# E-Slushy.net
KiCad netlist of a schematic drawn in EAGLE
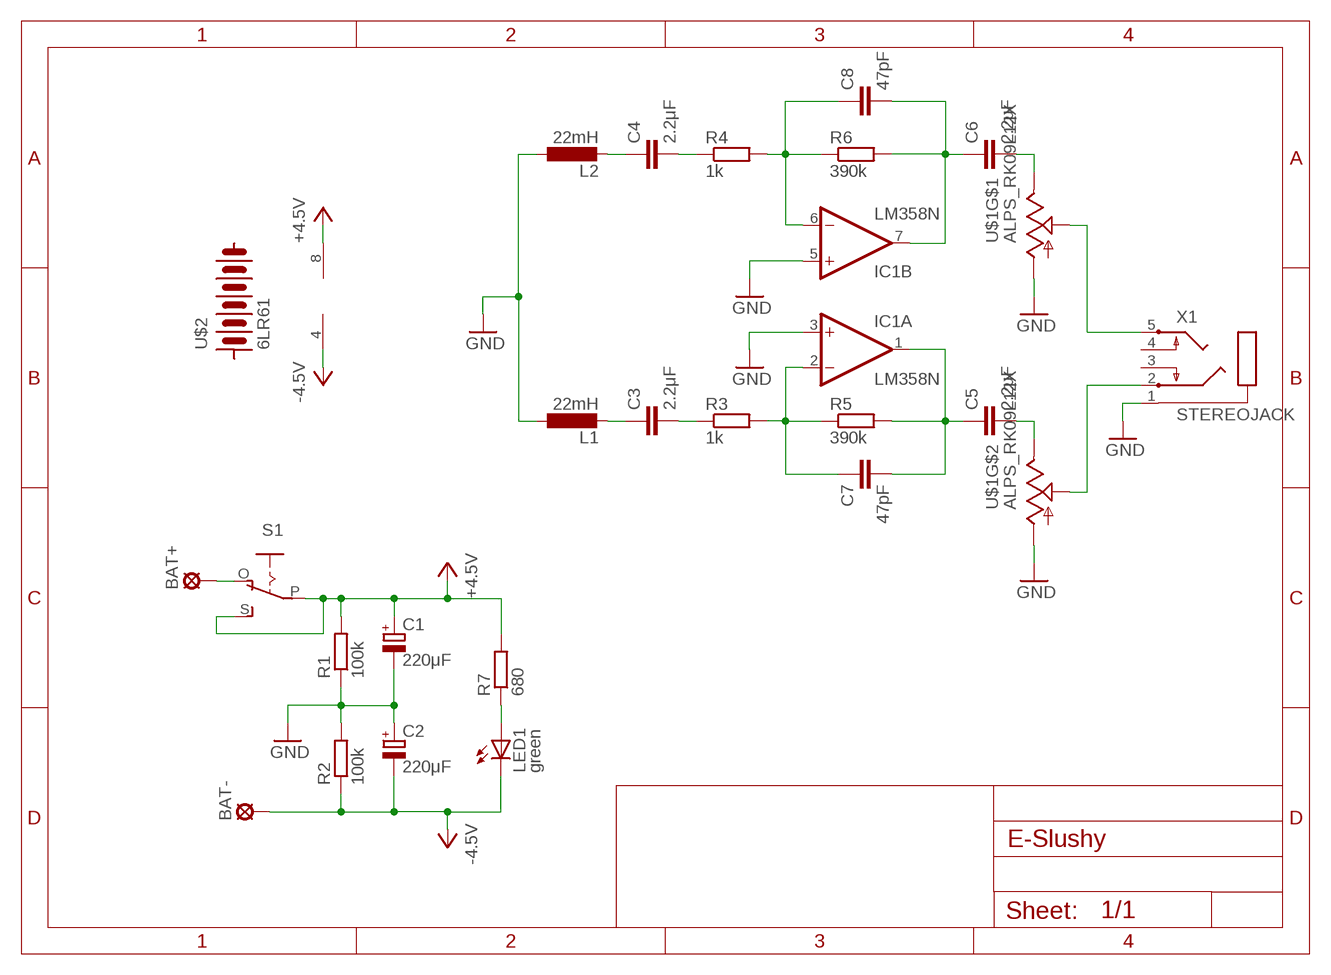
[diagram p0: schematic, sheet 1]

(export (version "E")
  (design (tool "Eeschema 10.0.6"))
  (components
    (comp (ref "BAT+")
      (value "SE14")
      (footprint "eagle-import:SE14")
      (libsource (lib "eagle-import") (part "SE14"))
    )
    (comp (ref "BAT-")
      (value "SE14")
      (footprint "eagle-import:SE14")
      (libsource (lib "eagle-import") (part "SE14"))
    )
    (comp (ref "C1")
      (value "220μF")
      (footprint "eagle-import:PANASONIC_D")
      (libsource (lib "eagle-import") (part "CPOL-EUD"))
    )
    (comp (ref "C2")
      (value "220μF")
      (footprint "eagle-import:PANASONIC_D")
      (libsource (lib "eagle-import") (part "CPOL-EUD"))
    )
    (comp (ref "C3")
      (value "2.2μF")
      (footprint "eagle-import:C1206K")
      (libsource (lib "eagle-import") (part "C-EUC1206K"))
    )
    (comp (ref "C4")
      (value "2.2μF")
      (footprint "eagle-import:C1206K")
      (libsource (lib "eagle-import") (part "C-EUC1206K"))
    )
    (comp (ref "C5")
      (value "2.2μF")
      (footprint "eagle-import:C1206K")
      (libsource (lib "eagle-import") (part "C-EUC1206K"))
    )
    (comp (ref "C6")
      (value "2.2μF")
      (footprint "eagle-import:C1206K")
      (libsource (lib "eagle-import") (part "C-EUC1206K"))
    )
    (comp (ref "C7")
      (value "47pF")
      (footprint "eagle-import:C1206K")
      (libsource (lib "eagle-import") (part "C-EUC1206K"))
    )
    (comp (ref "C8")
      (value "47pF")
      (footprint "eagle-import:C1206K")
      (libsource (lib "eagle-import") (part "C-EUC1206K"))
    )
    (comp (ref "IC1")
      (value "LM358N")
      (footprint "eagle-import:DIL08")
      (libsource (lib "eagle-import") (part "LM358N"))
    )
    (comp (ref "L1")
      (value "22mH")
      (footprint "eagle-import:6000-XXXX-RC")
      (libsource (lib "eagle-import") (part "L-EU6000-XXX-RC"))
    )
    (comp (ref "L2")
      (value "22mH")
      (footprint "eagle-import:6000-XXXX-RC")
      (libsource (lib "eagle-import") (part "L-EU6000-XXX-RC"))
    )
    (comp (ref "LED1")
      (value "green")
      (footprint "eagle-import:LED5MM")
      (libsource (lib "eagle-import") (part "LED5MM"))
    )
    (comp (ref "R1")
      (value "100k")
      (footprint "eagle-import:R1206")
      (libsource (lib "eagle-import") (part "R-EU_R1206"))
    )
    (comp (ref "R2")
      (value "100k")
      (footprint "eagle-import:R1206")
      (libsource (lib "eagle-import") (part "R-EU_R1206"))
    )
    (comp (ref "R3")
      (value "1k")
      (footprint "eagle-import:R1206")
      (libsource (lib "eagle-import") (part "R-EU_R1206"))
    )
    (comp (ref "R4")
      (value "1k")
      (footprint "eagle-import:R1206")
      (libsource (lib "eagle-import") (part "R-EU_R1206"))
    )
    (comp (ref "R5")
      (value "390k")
      (footprint "eagle-import:R1206")
      (libsource (lib "eagle-import") (part "R-EU_R1206"))
    )
    (comp (ref "R6")
      (value "390k")
      (footprint "eagle-import:R1206")
      (libsource (lib "eagle-import") (part "R-EU_R1206"))
    )
    (comp (ref "R7")
      (value "680")
      (footprint "eagle-import:R1206")
      (libsource (lib "eagle-import") (part "R-EU_R1206"))
    )
    (comp (ref "S1")
      (value "EG1218S")
      (footprint "eagle-import:EG1218")
      (libsource (lib "eagle-import") (part "EG1218S"))
    )
    (comp (ref "U$1")
      (value "ALPS_RK09L12X")
      (footprint "eagle-import:RK09L12")
      (libsource (lib "eagle-import") (part "ALPS_RK09L12X"))
    )
    (comp (ref "U$2")
      (value "6LR61")
      (footprint "eagle-import:6LR61")
      (libsource (lib "eagle-import") (part "6LR61"))
    )
    (comp (ref "X1")
      (value "STEREOJACK")
      (footprint "eagle-import:STX3100")
      (libsource (lib "eagle-import") (part "STEREOJACK"))
    )
  )
  (nets
    (net (code "1") (name "+4.5V") (class "Default")
      (node (ref "C1") (pin "+") (pinfunction "+_+") (pintype "passive"))
      (node (ref "IC1") (pin "8") (pinfunction "V+_8") (pintype "power_in"))
      (node (ref "R1") (pin "2") (pinfunction "2_2") (pintype "passive"))
      (node (ref "R7") (pin "2") (pinfunction "2_2") (pintype "passive"))
      (node (ref "S1") (pin "P") (pinfunction "P_P") (pintype "passive"))
      (node (ref "S1") (pin "S") (pinfunction "S_S") (pintype "passive"))
    )
    (net (code "2") (name "-4.5V") (class "Default")
      (node (ref "BAT-") (pin "MP") (pinfunction "MP_MP") (pintype "passive"))
      (node (ref "C2") (pin "-") (pinfunction "-_-") (pintype "passive"))
      (node (ref "IC1") (pin "4") (pinfunction "V-_4") (pintype "power_in"))
      (node (ref "LED1") (pin "K") (pinfunction "C_K") (pintype "passive"))
      (node (ref "R2") (pin "1") (pinfunction "1_1") (pintype "passive"))
    )
    (net (code "3") (name "GND") (class "Default")
      (node (ref "C1") (pin "-") (pinfunction "-_-") (pintype "passive"))
      (node (ref "C2") (pin "+") (pinfunction "+_+") (pintype "passive"))
      (node (ref "IC1") (pin "3") (pinfunction "+IN_3") (pintype "input"))
      (node (ref "IC1") (pin "5") (pinfunction "+IN_5") (pintype "input"))
      (node (ref "L1") (pin "1") (pinfunction "1_1") (pintype "passive"))
      (node (ref "L2") (pin "1") (pinfunction "1_1") (pintype "passive"))
      (node (ref "R1") (pin "1") (pinfunction "1_1") (pintype "passive"))
      (node (ref "R2") (pin "2") (pinfunction "2_2") (pintype "passive"))
      (node (ref "U$1") (pin "A1") (pinfunction "1_A1") (pintype "passive"))
      (node (ref "U$1") (pin "B1") (pinfunction "1_B1") (pintype "passive"))
      (node (ref "X1") (pin "1") (pinfunction "1_1") (pintype "passive"))
    )
    (net (code "4") (name "Net-(BAT+-PadMP)") (class "Default")
      (node (ref "BAT+") (pin "MP") (pinfunction "MP_MP") (pintype "passive"))
      (node (ref "S1") (pin "O") (pinfunction "O_O") (pintype "passive"))
    )
    (net (code "5") (name "Net-(C3-Pad1)") (class "Default")
      (node (ref "C3") (pin "1") (pinfunction "1_1") (pintype "passive"))
      (node (ref "L1") (pin "2") (pinfunction "2_2") (pintype "passive"))
    )
    (net (code "6") (name "Net-(C3-Pad2)") (class "Default")
      (node (ref "C3") (pin "2") (pinfunction "2_2") (pintype "passive"))
      (node (ref "R3") (pin "1") (pinfunction "1_1") (pintype "passive"))
    )
    (net (code "7") (name "Net-(C4-Pad1)") (class "Default")
      (node (ref "C4") (pin "1") (pinfunction "1_1") (pintype "passive"))
      (node (ref "L2") (pin "2") (pinfunction "2_2") (pintype "passive"))
    )
    (net (code "8") (name "Net-(C4-Pad2)") (class "Default")
      (node (ref "C4") (pin "2") (pinfunction "2_2") (pintype "passive"))
      (node (ref "R4") (pin "1") (pinfunction "1_1") (pintype "passive"))
    )
    (net (code "9") (name "Net-(IC1A--IN)") (class "Default")
      (node (ref "C7") (pin "1") (pinfunction "1_1") (pintype "passive"))
      (node (ref "IC1") (pin "2") (pinfunction "-IN_2") (pintype "input"))
      (node (ref "R3") (pin "2") (pinfunction "2_2") (pintype "passive"))
      (node (ref "R5") (pin "1") (pinfunction "1_1") (pintype "passive"))
    )
    (net (code "10") (name "Net-(IC1A-OUT)") (class "Default")
      (node (ref "C5") (pin "1") (pinfunction "1_1") (pintype "passive"))
      (node (ref "C7") (pin "2") (pinfunction "2_2") (pintype "passive"))
      (node (ref "IC1") (pin "1") (pinfunction "OUT_1") (pintype "output"))
      (node (ref "R5") (pin "2") (pinfunction "2_2") (pintype "passive"))
    )
    (net (code "11") (name "Net-(IC1B--IN)") (class "Default")
      (node (ref "C8") (pin "1") (pinfunction "1_1") (pintype "passive"))
      (node (ref "IC1") (pin "6") (pinfunction "-IN_6") (pintype "input"))
      (node (ref "R4") (pin "2") (pinfunction "2_2") (pintype "passive"))
      (node (ref "R6") (pin "1") (pinfunction "1_1") (pintype "passive"))
    )
    (net (code "12") (name "Net-(IC1B-OUT)") (class "Default")
      (node (ref "C6") (pin "1") (pinfunction "1_1") (pintype "passive"))
      (node (ref "C8") (pin "2") (pinfunction "2_2") (pintype "passive"))
      (node (ref "IC1") (pin "7") (pinfunction "OUT_7") (pintype "output"))
      (node (ref "R6") (pin "2") (pinfunction "2_2") (pintype "passive"))
    )
    (net (code "13") (name "Net-(LED1-PadA)") (class "Default")
      (node (ref "LED1") (pin "A") (pinfunction "A_A") (pintype "passive"))
      (node (ref "R7") (pin "1") (pinfunction "1_1") (pintype "passive"))
    )
    (net (code "14") (name "Net-(U$1A-2)") (class "Default")
      (node (ref "U$1") (pin "A2") (pinfunction "2_A2") (pintype "passive"))
      (node (ref "X1") (pin "5") (pinfunction "5_5") (pintype "passive"))
    )
    (net (code "15") (name "Net-(U$1A-3)") (class "Default")
      (node (ref "C6") (pin "2") (pinfunction "2_2") (pintype "passive"))
      (node (ref "U$1") (pin "A3") (pinfunction "3_A3") (pintype "passive"))
    )
    (net (code "16") (name "Net-(U$1B-2)") (class "Default")
      (node (ref "U$1") (pin "B2") (pinfunction "2_B2") (pintype "passive"))
      (node (ref "X1") (pin "2") (pinfunction "2_2") (pintype "passive"))
    )
    (net (code "17") (name "Net-(U$1B-3)") (class "Default")
      (node (ref "C5") (pin "2") (pinfunction "2_2") (pintype "passive"))
      (node (ref "U$1") (pin "B3") (pinfunction "3_B3") (pintype "passive"))
    )
    (net (code "18") (name "unconnected-(X1-Pad3)") (class "Default")
      (node (ref "X1") (pin "3") (pinfunction "3_3") (pintype "passive"))
    )
    (net (code "19") (name "unconnected-(X1-Pad4)") (class "Default")
      (node (ref "X1") (pin "4") (pinfunction "4_4") (pintype "passive"))
    )
  )
)
